# LV_Board.net
KiCad netlist of a schematic drawn in Altium Designer
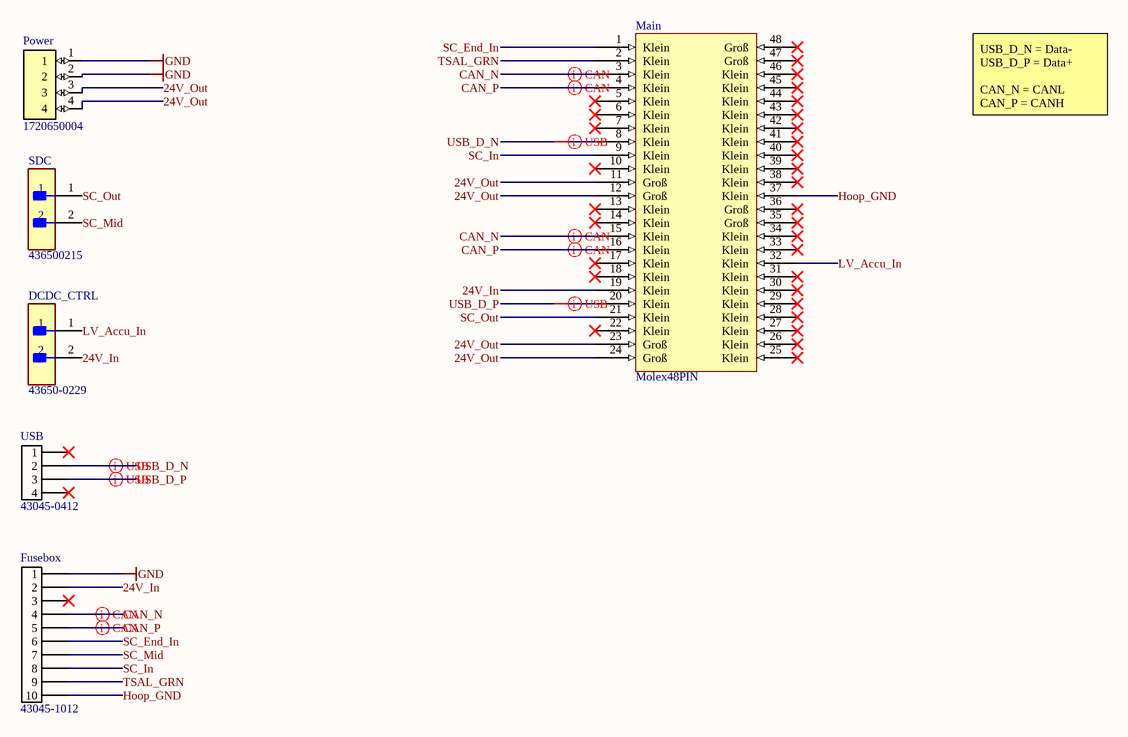
[diagram p0: LV_Board.SchDoc]

(export (version "E")
  (design (tool "Eeschema 10.0.6"))
  (components
    (comp (ref "DCDC_CTRL")
      (value "43650-0229")
      (footprint "436500229")
      (description "Micro-Fit 3.0 Vertical Header, 3.00mm Pitch, Single Row, 2 Circuits")
      (libsource (lib "LibMoritz") (part "43650-0229"))
    )
    (comp (ref "Fusebox")
      (value "43045-1012")
      (footprint "43045-1012")
      (libsource (lib "molex_43045") (part "43045-1012"))
    )
    (comp (ref "Main")
      (value "Molex48PIN")
      (footprint "Molex 48 Pin Header CMC/CMX")
      (libsource (lib "Integrated_LibraryLukas_New") (part "Molex48PIN"))
    )
    (comp (ref "Power")
      (value "1720650004")
      (footprint "1720650004")
      (description "Mega-Fit Vertical Header, Through Hole, 5.70mm Pitch, Dual Row, 4 Circuits, 0.38µm")
      (libsource (lib "LibMoritz") (part "1720650004"))
    )
    (comp (ref "SDC")
      (value "436500215")
      (footprint "436500215")
      (description "Micro-Fit 3.0 Vertical Header, 3.00mm Pitch, Single Row, 2 Circuits")
      (libsource (lib "LibMoritz") (part "436500215"))
    )
    (comp (ref "USB")
      (value "43045-0412")
      (footprint "43045-0412")
      (libsource (lib "molex_43045") (part "43045-0412"))
    )
  )
  (nets
    (net (code "1") (name "/24V_In") (class "Default")
      (node (ref "DCDC_CTRL") (pin "2") (pinfunction "2_2") (pintype "passive"))
      (node (ref "Fusebox") (pin "2") (pinfunction "2_2") (pintype "passive"))
      (node (ref "Main") (pin "19") (pinfunction "Klein_19") (pintype "input"))
    )
    (net (code "2") (name "/24V_Out") (class "Default")
      (node (ref "Main") (pin "11") (pinfunction "Groß_11") (pintype "input"))
      (node (ref "Main") (pin "12") (pinfunction "Groß_12") (pintype "input"))
      (node (ref "Main") (pin "23") (pinfunction "Groß_23") (pintype "input"))
      (node (ref "Main") (pin "24") (pinfunction "Groß_24") (pintype "input"))
      (node (ref "Power") (pin "3") (pinfunction "3_3") (pintype "bidirectional"))
      (node (ref "Power") (pin "4") (pinfunction "4_4") (pintype "bidirectional"))
    )
    (net (code "3") (name "/CAN_N") (class "Default")
      (node (ref "Fusebox") (pin "4") (pinfunction "4_4") (pintype "passive"))
      (node (ref "Main") (pin "15") (pinfunction "Klein_15") (pintype "input"))
      (node (ref "Main") (pin "3") (pinfunction "Klein_3") (pintype "input"))
    )
    (net (code "4") (name "/CAN_P") (class "Default")
      (node (ref "Fusebox") (pin "5") (pinfunction "5_5") (pintype "passive"))
      (node (ref "Main") (pin "16") (pinfunction "Klein_16") (pintype "input"))
      (node (ref "Main") (pin "4") (pinfunction "Klein_4") (pintype "input"))
    )
    (net (code "5") (name "/Hoop_GND") (class "Default")
      (node (ref "Fusebox") (pin "10") (pinfunction "10_10") (pintype "passive"))
      (node (ref "Main") (pin "37") (pinfunction "Klein_37") (pintype "input"))
    )
    (net (code "6") (name "/LV_Accu_In") (class "Default")
      (node (ref "DCDC_CTRL") (pin "1") (pinfunction "1_1") (pintype "passive"))
      (node (ref "Main") (pin "32") (pinfunction "Klein_32") (pintype "input"))
    )
    (net (code "7") (name "/SC_End_In") (class "Default")
      (node (ref "Fusebox") (pin "6") (pinfunction "6_6") (pintype "passive"))
      (node (ref "Main") (pin "1") (pinfunction "Klein_1") (pintype "input"))
    )
    (net (code "8") (name "/SC_In") (class "Default")
      (node (ref "Fusebox") (pin "8") (pinfunction "8_8") (pintype "passive"))
      (node (ref "Main") (pin "9") (pinfunction "Klein_9") (pintype "input"))
    )
    (net (code "9") (name "/SC_Mid") (class "Default")
      (node (ref "Fusebox") (pin "7") (pinfunction "7_7") (pintype "passive"))
      (node (ref "SDC") (pin "2") (pinfunction "2_2") (pintype "passive"))
    )
    (net (code "10") (name "/SC_Out") (class "Default")
      (node (ref "Main") (pin "21") (pinfunction "Klein_21") (pintype "input"))
      (node (ref "SDC") (pin "1") (pinfunction "1_1") (pintype "passive"))
    )
    (net (code "11") (name "/TSAL_GRN") (class "Default")
      (node (ref "Fusebox") (pin "9") (pinfunction "9_9") (pintype "passive"))
      (node (ref "Main") (pin "2") (pinfunction "Klein_2") (pintype "input"))
    )
    (net (code "12") (name "/USB_D_N") (class "Default")
      (node (ref "Main") (pin "8") (pinfunction "Klein_8") (pintype "input"))
      (node (ref "USB") (pin "2") (pinfunction "2_2") (pintype "passive"))
    )
    (net (code "13") (name "/USB_D_P") (class "Default")
      (node (ref "Main") (pin "20") (pinfunction "Klein_20") (pintype "input"))
      (node (ref "USB") (pin "3") (pinfunction "3_3") (pintype "passive"))
    )
    (net (code "14") (name "GND") (class "Default")
      (node (ref "Fusebox") (pin "1") (pinfunction "1_1") (pintype "passive"))
      (node (ref "Power") (pin "1") (pinfunction "1_1") (pintype "bidirectional"))
      (node (ref "Power") (pin "2") (pinfunction "2_2") (pintype "bidirectional"))
    )
    (net (code "15") (name "unconnected-(Fusebox-Pad3)") (class "Default")
      (node (ref "Fusebox") (pin "3") (pinfunction "3_3") (pintype "passive+no_connect"))
    )
    (net (code "16") (name "unconnected-(Main-Groß-Pad35)") (class "Default")
      (node (ref "Main") (pin "35") (pinfunction "Groß_35") (pintype "input+no_connect"))
    )
    (net (code "17") (name "unconnected-(Main-Groß-Pad36)") (class "Default")
      (node (ref "Main") (pin "36") (pinfunction "Groß_36") (pintype "input+no_connect"))
    )
    (net (code "18") (name "unconnected-(Main-Groß-Pad47)") (class "Default")
      (node (ref "Main") (pin "47") (pinfunction "Groß_47") (pintype "input+no_connect"))
    )
    (net (code "19") (name "unconnected-(Main-Groß-Pad48)") (class "Default")
      (node (ref "Main") (pin "48") (pinfunction "Groß_48") (pintype "input+no_connect"))
    )
    (net (code "20") (name "unconnected-(Main-Klein-Pad5)") (class "Default")
      (node (ref "Main") (pin "5") (pinfunction "Klein_5") (pintype "input+no_connect"))
    )
    (net (code "21") (name "unconnected-(Main-Klein-Pad6)") (class "Default")
      (node (ref "Main") (pin "6") (pinfunction "Klein_6") (pintype "input+no_connect"))
    )
    (net (code "22") (name "unconnected-(Main-Klein-Pad7)") (class "Default")
      (node (ref "Main") (pin "7") (pinfunction "Klein_7") (pintype "input+no_connect"))
    )
    (net (code "23") (name "unconnected-(Main-Klein-Pad10)") (class "Default")
      (node (ref "Main") (pin "10") (pinfunction "Klein_10") (pintype "input+no_connect"))
    )
    (net (code "24") (name "unconnected-(Main-Klein-Pad13)") (class "Default")
      (node (ref "Main") (pin "13") (pinfunction "Klein_13") (pintype "input+no_connect"))
    )
    (net (code "25") (name "unconnected-(Main-Klein-Pad14)") (class "Default")
      (node (ref "Main") (pin "14") (pinfunction "Klein_14") (pintype "input+no_connect"))
    )
    (net (code "26") (name "unconnected-(Main-Klein-Pad17)") (class "Default")
      (node (ref "Main") (pin "17") (pinfunction "Klein_17") (pintype "input+no_connect"))
    )
    (net (code "27") (name "unconnected-(Main-Klein-Pad18)") (class "Default")
      (node (ref "Main") (pin "18") (pinfunction "Klein_18") (pintype "input+no_connect"))
    )
    (net (code "28") (name "unconnected-(Main-Klein-Pad22)") (class "Default")
      (node (ref "Main") (pin "22") (pinfunction "Klein_22") (pintype "input+no_connect"))
    )
    (net (code "29") (name "unconnected-(Main-Klein-Pad25)") (class "Default")
      (node (ref "Main") (pin "25") (pinfunction "Klein_25") (pintype "input+no_connect"))
    )
    (net (code "30") (name "unconnected-(Main-Klein-Pad26)") (class "Default")
      (node (ref "Main") (pin "26") (pinfunction "Klein_26") (pintype "input+no_connect"))
    )
    (net (code "31") (name "unconnected-(Main-Klein-Pad27)") (class "Default")
      (node (ref "Main") (pin "27") (pinfunction "Klein_27") (pintype "input+no_connect"))
    )
    (net (code "32") (name "unconnected-(Main-Klein-Pad28)") (class "Default")
      (node (ref "Main") (pin "28") (pinfunction "Klein_28") (pintype "input+no_connect"))
    )
    (net (code "33") (name "unconnected-(Main-Klein-Pad29)") (class "Default")
      (node (ref "Main") (pin "29") (pinfunction "Klein_29") (pintype "input+no_connect"))
    )
    (net (code "34") (name "unconnected-(Main-Klein-Pad30)") (class "Default")
      (node (ref "Main") (pin "30") (pinfunction "Klein_30") (pintype "input+no_connect"))
    )
    (net (code "35") (name "unconnected-(Main-Klein-Pad31)") (class "Default")
      (node (ref "Main") (pin "31") (pinfunction "Klein_31") (pintype "input+no_connect"))
    )
    (net (code "36") (name "unconnected-(Main-Klein-Pad33)") (class "Default")
      (node (ref "Main") (pin "33") (pinfunction "Klein_33") (pintype "input+no_connect"))
    )
    (net (code "37") (name "unconnected-(Main-Klein-Pad34)") (class "Default")
      (node (ref "Main") (pin "34") (pinfunction "Klein_34") (pintype "input+no_connect"))
    )
    (net (code "38") (name "unconnected-(Main-Klein-Pad38)") (class "Default")
      (node (ref "Main") (pin "38") (pinfunction "Klein_38") (pintype "input+no_connect"))
    )
    (net (code "39") (name "unconnected-(Main-Klein-Pad39)") (class "Default")
      (node (ref "Main") (pin "39") (pinfunction "Klein_39") (pintype "input+no_connect"))
    )
    (net (code "40") (name "unconnected-(Main-Klein-Pad40)") (class "Default")
      (node (ref "Main") (pin "40") (pinfunction "Klein_40") (pintype "input+no_connect"))
    )
    (net (code "41") (name "unconnected-(Main-Klein-Pad41)") (class "Default")
      (node (ref "Main") (pin "41") (pinfunction "Klein_41") (pintype "input+no_connect"))
    )
    (net (code "42") (name "unconnected-(Main-Klein-Pad42)") (class "Default")
      (node (ref "Main") (pin "42") (pinfunction "Klein_42") (pintype "input+no_connect"))
    )
    (net (code "43") (name "unconnected-(Main-Klein-Pad43)") (class "Default")
      (node (ref "Main") (pin "43") (pinfunction "Klein_43") (pintype "input+no_connect"))
    )
    (net (code "44") (name "unconnected-(Main-Klein-Pad44)") (class "Default")
      (node (ref "Main") (pin "44") (pinfunction "Klein_44") (pintype "input+no_connect"))
    )
    (net (code "45") (name "unconnected-(Main-Klein-Pad45)") (class "Default")
      (node (ref "Main") (pin "45") (pinfunction "Klein_45") (pintype "input+no_connect"))
    )
    (net (code "46") (name "unconnected-(Main-Klein-Pad46)") (class "Default")
      (node (ref "Main") (pin "46") (pinfunction "Klein_46") (pintype "input+no_connect"))
    )
    (net (code "47") (name "unconnected-(USB-Pad1)") (class "Default")
      (node (ref "USB") (pin "1") (pinfunction "1_1") (pintype "passive+no_connect"))
    )
    (net (code "48") (name "unconnected-(USB-Pad4)") (class "Default")
      (node (ref "USB") (pin "4") (pinfunction "4_4") (pintype "passive+no_connect"))
    )
  )
)
